# Nixie_Power_Suppy_v2_0_2.net
KiCad netlist of a schematic drawn in EAGLE
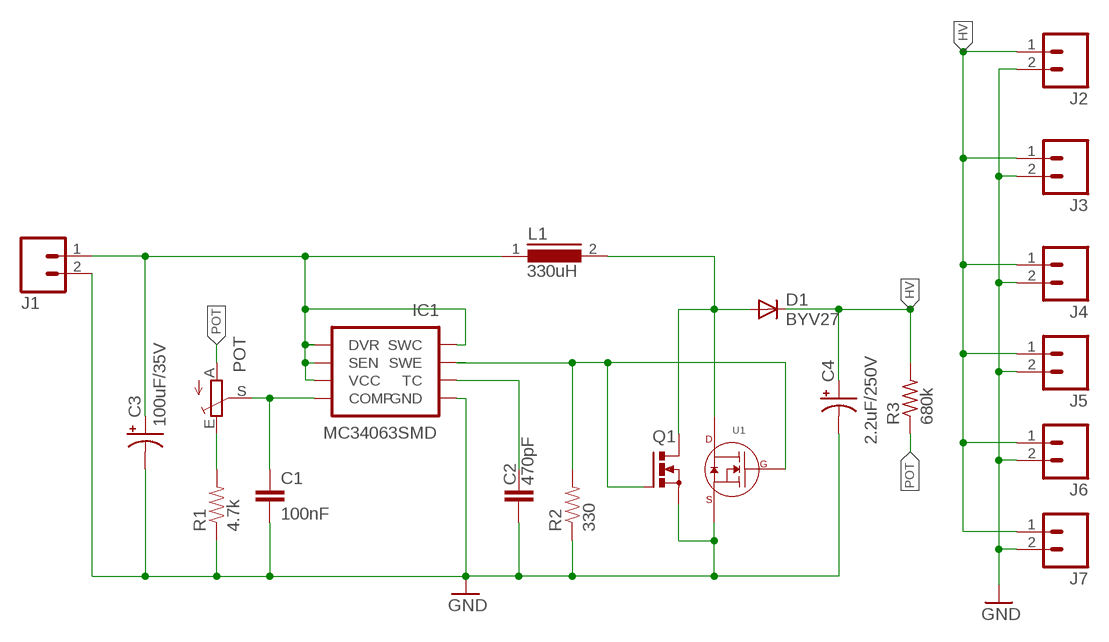
[diagram p0: schematic, sheet 1]

(export (version "E")
  (design (tool "Eeschema 10.0.6"))
  (components
    (comp (ref "C1")
      (value "100nF")
      (footprint "eagle-import:0805")
      (libsource (lib "eagle-import") (part "CAP0805"))
    )
    (comp (ref "C2")
      (value "470pF")
      (footprint "eagle-import:0805")
      (libsource (lib "eagle-import") (part "CAP0805"))
    )
    (comp (ref "C3")
      (value "100uF/35V")
      (footprint "eagle-import:CPOL-RADIAL-100UF-25V")
      (libsource (lib "eagle-import") (part "CAP_POLPTH1"))
    )
    (comp (ref "C4")
      (value "2.2uF/250V")
      (footprint "eagle-import:CPOL-RADIAL-100UF-25V")
      (libsource (lib "eagle-import") (part "CAP_POLPTH1"))
    )
    (comp (ref "D1")
      (value "BYV27")
      (footprint "eagle-import:SOD57-10")
      (libsource (lib "eagle-import") (part "BYV27"))
    )
    (comp (ref "IC1")
      (value "MC34063SMD")
      (footprint "eagle-import:SO08")
      (libsource (lib "eagle-import") (part "MC34063SMD"))
    )
    (comp (ref "J1")
      (value "M02LOCK")
      (footprint "eagle-import:1X02_LOCK")
      (libsource (lib "eagle-import") (part "M02LOCK"))
    )
    (comp (ref "J2")
      (value "M02LOCK")
      (footprint "eagle-import:1X02_LOCK")
      (libsource (lib "eagle-import") (part "M02LOCK"))
    )
    (comp (ref "J3")
      (value "M02LOCK")
      (footprint "eagle-import:1X02_LOCK")
      (libsource (lib "eagle-import") (part "M02LOCK"))
    )
    (comp (ref "J4")
      (value "M02LOCK")
      (footprint "eagle-import:1X02_LOCK")
      (libsource (lib "eagle-import") (part "M02LOCK"))
    )
    (comp (ref "J5")
      (value "M02LOCK")
      (footprint "eagle-import:1X02_LOCK")
      (libsource (lib "eagle-import") (part "M02LOCK"))
    )
    (comp (ref "J6")
      (value "M02LOCK")
      (footprint "eagle-import:1X02_LOCK")
      (libsource (lib "eagle-import") (part "M02LOCK"))
    )
    (comp (ref "J7")
      (value "M02LOCK")
      (footprint "eagle-import:1X02_LOCK")
      (libsource (lib "eagle-import") (part "M02LOCK"))
    )
    (comp (ref "L1")
      (value "330uH")
      (footprint "eagle-import:DR74")
      (libsource (lib "eagle-import") (part "DR74"))
    )
    (comp (ref "POT")
      (value "TRIM_EU-CA6V")
      (footprint "eagle-import:CA6V")
      (libsource (lib "eagle-import") (part "TRIM_EU-CA6V"))
    )
    (comp (ref "Q1")
      (value "PMOSFET_NTO220BV")
      (footprint "eagle-import:TO220BV")
      (libsource (lib "eagle-import") (part "PMOSFET_NTO220BV"))
    )
    (comp (ref "R1")
      (value "4.7k")
      (footprint "eagle-import:0805")
      (libsource (lib "eagle-import") (part "RESISTOR0805-RES"))
    )
    (comp (ref "R2")
      (value "330")
      (footprint "eagle-import:0805")
      (libsource (lib "eagle-import") (part "RESISTOR0805-RES"))
    )
    (comp (ref "R3")
      (value "680k")
      (footprint "eagle-import:M1206")
      (libsource (lib "eagle-import") (part "R-US_M1206"))
    )
    (comp (ref "U1")
      (value "MOSFET_N-CHANNEL_SINGLE_TO-252-3")
      (footprint "eagle-import:TO-252-3")
      (libsource (lib "eagle-import") (part "MOSFET_N-CHANNEL_SINGLE_TO-252-3"))
    )
  )
  (nets
    (net (code "1") (name "GND") (class "Default")
      (node (ref "C1") (pin "2") (pinfunction "2_2") (pintype "passive"))
      (node (ref "C2") (pin "2") (pinfunction "2_2") (pintype "passive"))
      (node (ref "C3") (pin "2") (pinfunction "-_2") (pintype "passive"))
      (node (ref "C4") (pin "2") (pinfunction "-_2") (pintype "passive"))
      (node (ref "IC1") (pin "4") (pinfunction "GND_4") (pintype "bidirectional"))
      (node (ref "J1") (pin "2") (pinfunction "2_2") (pintype "passive"))
      (node (ref "J2") (pin "2") (pinfunction "2_2") (pintype "passive"))
      (node (ref "J3") (pin "2") (pinfunction "2_2") (pintype "passive"))
      (node (ref "J4") (pin "2") (pinfunction "2_2") (pintype "passive"))
      (node (ref "J5") (pin "2") (pinfunction "2_2") (pintype "passive"))
      (node (ref "J6") (pin "2") (pinfunction "2_2") (pintype "passive"))
      (node (ref "J7") (pin "2") (pinfunction "2_2") (pintype "passive"))
      (node (ref "Q1") (pin "S") (pinfunction "S_S") (pintype "passive"))
      (node (ref "R1") (pin "1") (pinfunction "1_1") (pintype "passive"))
      (node (ref "R2") (pin "1") (pinfunction "1_1") (pintype "passive"))
      (node (ref "U1") (pin "3") (pinfunction "SOURCE_3") (pintype "bidirectional"))
    )
    (net (code "2") (name "HV") (class "Default")
      (node (ref "C4") (pin "1") (pinfunction "+_1") (pintype "passive"))
      (node (ref "D1") (pin "C") (pinfunction "C_C") (pintype "passive"))
      (node (ref "J2") (pin "1") (pinfunction "1_1") (pintype "passive"))
      (node (ref "J3") (pin "1") (pinfunction "1_1") (pintype "passive"))
      (node (ref "J4") (pin "1") (pinfunction "1_1") (pintype "passive"))
      (node (ref "J5") (pin "1") (pinfunction "1_1") (pintype "passive"))
      (node (ref "J6") (pin "1") (pinfunction "1_1") (pintype "passive"))
      (node (ref "J7") (pin "1") (pinfunction "1_1") (pintype "passive"))
      (node (ref "R3") (pin "2") (pinfunction "2_2") (pintype "passive"))
    )
    (net (code "3") (name "Net-(C3-+)") (class "Default")
      (node (ref "C3") (pin "1") (pinfunction "+_1") (pintype "passive"))
      (node (ref "IC1") (pin "1") (pinfunction "SWC_1") (pintype "bidirectional"))
      (node (ref "IC1") (pin "6") (pinfunction "VCC_6") (pintype "bidirectional"))
      (node (ref "IC1") (pin "7") (pinfunction "SEN_7") (pintype "bidirectional"))
      (node (ref "IC1") (pin "8") (pinfunction "DVR_8") (pintype "bidirectional"))
      (node (ref "J1") (pin "1") (pinfunction "1_1") (pintype "passive"))
      (node (ref "L1") (pin "1") (pinfunction "1_1") (pintype "passive"))
    )
    (net (code "4") (name "Net-(IC1-COMP)") (class "Default")
      (node (ref "C1") (pin "1") (pinfunction "1_1") (pintype "passive"))
      (node (ref "IC1") (pin "5") (pinfunction "COMP_5") (pintype "bidirectional"))
      (node (ref "POT") (pin "S") (pinfunction "S_S") (pintype "passive"))
    )
    (net (code "5") (name "Net-(IC1-SWE)") (class "Default")
      (node (ref "IC1") (pin "2") (pinfunction "SWE_2") (pintype "bidirectional"))
      (node (ref "Q1") (pin "G") (pinfunction "G_G") (pintype "passive"))
      (node (ref "R2") (pin "2") (pinfunction "2_2") (pintype "passive"))
      (node (ref "U1") (pin "1") (pinfunction "GATE_1") (pintype "bidirectional"))
    )
    (net (code "6") (name "Net-(IC1-TC)") (class "Default")
      (node (ref "C2") (pin "1") (pinfunction "1_1") (pintype "passive"))
      (node (ref "IC1") (pin "3") (pinfunction "TC_3") (pintype "bidirectional"))
    )
    (net (code "7") (name "Net-(POT-PadE)") (class "Default")
      (node (ref "POT") (pin "E") (pinfunction "E_E") (pintype "passive"))
      (node (ref "R1") (pin "2") (pinfunction "2_2") (pintype "passive"))
    )
    (net (code "8") (name "Net-(U1-DRAIN)") (class "Default")
      (node (ref "D1") (pin "A") (pinfunction "A_A") (pintype "passive"))
      (node (ref "L1") (pin "2") (pinfunction "2_2") (pintype "passive"))
      (node (ref "Q1") (pin "D") (pinfunction "D_D") (pintype "passive"))
      (node (ref "U1") (pin "PAD") (pinfunction "DRAIN_PAD") (pintype "bidirectional"))
    )
    (net (code "9") (name "POT") (class "Default")
      (node (ref "POT") (pin "A") (pinfunction "A_A") (pintype "passive"))
      (node (ref "R3") (pin "1") (pinfunction "1_1") (pintype "passive"))
    )
  )
)
